# FieldsControls.net
KiCad netlist of a schematic drawn in EAGLE
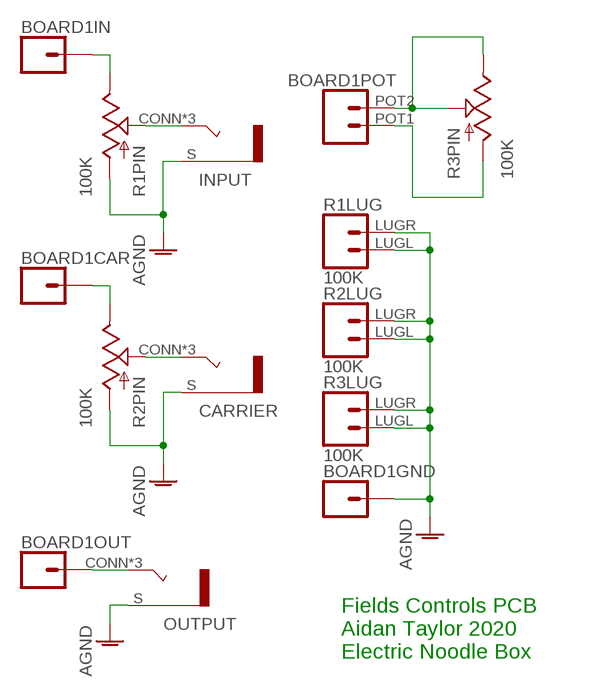
[diagram p0: schematic, sheet 1]

(export (version "E")
  (design (tool "Eeschema 10.0.6"))
  (components
    (comp (ref "BOARD1")
      (value "FIELDS_LINK")
      (footprint "eagle-import:FIELDS")
      (libsource (lib "eagle-import") (part "FIELDS_LINK"))
    )
    (comp (ref "CARRIER")
      (value "COMBI-JACKCINCHNANA")
      (footprint "eagle-import:NEWCOMBOJACK_PANEL")
      (libsource (lib "eagle-import") (part "COMBI-JACKCINCHNANA"))
    )
    (comp (ref "INPUT")
      (value "COMBI-JACKCINCHNANA")
      (footprint "eagle-import:NEWCOMBOJACK_PANEL")
      (libsource (lib "eagle-import") (part "COMBI-JACKCINCHNANA"))
    )
    (comp (ref "OUTPUT")
      (value "COMBI-JACKCINCHNANA")
      (footprint "eagle-import:NEWCOMBOJACK_PANEL")
      (libsource (lib "eagle-import") (part "COMBI-JACKCINCHNANA"))
    )
    (comp (ref "R1")
      (value "100K")
      (footprint "eagle-import:ALPHA_RV09_9MMPOT")
      (libsource (lib "eagle-import") (part "POTENTIOMETER"))
    )
    (comp (ref "R2")
      (value "100K")
      (footprint "eagle-import:ALPHA_RV09_9MMPOT")
      (libsource (lib "eagle-import") (part "POTENTIOMETER"))
    )
    (comp (ref "R3")
      (value "100K")
      (footprint "eagle-import:ALPHA_RV09_9MMPOT")
      (libsource (lib "eagle-import") (part "POTENTIOMETER"))
    )
  )
  (nets
    (net (code "1") (name "AGND") (class "Default")
      (node (ref "BOARD1") (pin "GND") (pinfunction "1_GND") (pintype "passive"))
      (node (ref "BOARD1") (pin "GND2") (pinfunction "1_GND2") (pintype "passive"))
      (node (ref "CARRIER") (pin "S") (pinfunction "S_S") (pintype "passive"))
      (node (ref "INPUT") (pin "S") (pinfunction "S_S") (pintype "passive"))
      (node (ref "OUTPUT") (pin "S") (pinfunction "S_S") (pintype "passive"))
      (node (ref "R1") (pin "C1") (pinfunction "A_C1") (pintype "passive"))
      (node (ref "R1") (pin "LUGL") (pinfunction "1_LUGL") (pintype "passive"))
      (node (ref "R1") (pin "LUGR") (pinfunction "2_LUGR") (pintype "passive"))
      (node (ref "R2") (pin "C1") (pinfunction "A_C1") (pintype "passive"))
      (node (ref "R2") (pin "LUGL") (pinfunction "1_LUGL") (pintype "passive"))
      (node (ref "R2") (pin "LUGR") (pinfunction "2_LUGR") (pintype "passive"))
      (node (ref "R3") (pin "LUGL") (pinfunction "1_LUGL") (pintype "passive"))
      (node (ref "R3") (pin "LUGR") (pinfunction "2_LUGR") (pintype "passive"))
    )
    (net (code "2") (name "Net-(BOARD1A-1)") (class "Default")
      (node (ref "BOARD1") (pin "CAR") (pinfunction "1_CAR") (pintype "passive"))
      (node (ref "R2") (pin "C3") (pinfunction "B_C3") (pintype "passive"))
    )
    (net (code "3") (name "Net-(BOARD1C-1)") (class "Default")
      (node (ref "BOARD1") (pin "IN") (pinfunction "1_IN") (pintype "passive"))
      (node (ref "R1") (pin "C3") (pinfunction "B_C3") (pintype "passive"))
    )
    (net (code "4") (name "Net-(BOARD1D-1)") (class "Default")
      (node (ref "BOARD1") (pin "OUT") (pinfunction "1_OUT") (pintype "passive"))
      (node (ref "OUTPUT") (pin "CONN") (pinfunction "T_CONN") (pintype "passive"))
      (node (ref "OUTPUT") (pin "T1") (pinfunction "T_T1") (pintype "passive"))
      (node (ref "OUTPUT") (pin "T2") (pinfunction "T_T2") (pintype "passive"))
    )
    (net (code "5") (name "Net-(BOARD1E-1)") (class "Default")
      (node (ref "BOARD1") (pin "POT1") (pinfunction "1_POT1") (pintype "passive"))
      (node (ref "R3") (pin "C1") (pinfunction "A_C1") (pintype "passive"))
    )
    (net (code "6") (name "Net-(BOARD1E-2)") (class "Default")
      (node (ref "BOARD1") (pin "POT2") (pinfunction "2_POT2") (pintype "passive"))
      (node (ref "R3") (pin "C2") (pinfunction "W_C2") (pintype "passive"))
      (node (ref "R3") (pin "C3") (pinfunction "B_C3") (pintype "passive"))
    )
    (net (code "7") (name "Net-(R1B-W)") (class "Default")
      (node (ref "INPUT") (pin "CONN") (pinfunction "T_CONN") (pintype "passive"))
      (node (ref "INPUT") (pin "T1") (pinfunction "T_T1") (pintype "passive"))
      (node (ref "INPUT") (pin "T2") (pinfunction "T_T2") (pintype "passive"))
      (node (ref "R1") (pin "C2") (pinfunction "W_C2") (pintype "passive"))
    )
    (net (code "8") (name "Net-(R2B-W)") (class "Default")
      (node (ref "CARRIER") (pin "CONN") (pinfunction "T_CONN") (pintype "passive"))
      (node (ref "CARRIER") (pin "T1") (pinfunction "T_T1") (pintype "passive"))
      (node (ref "CARRIER") (pin "T2") (pinfunction "T_T2") (pintype "passive"))
      (node (ref "R2") (pin "C2") (pinfunction "W_C2") (pintype "passive"))
    )
  )
)
